# KCVGA_1_1.net
KiCad netlist of a schematic drawn in EAGLE
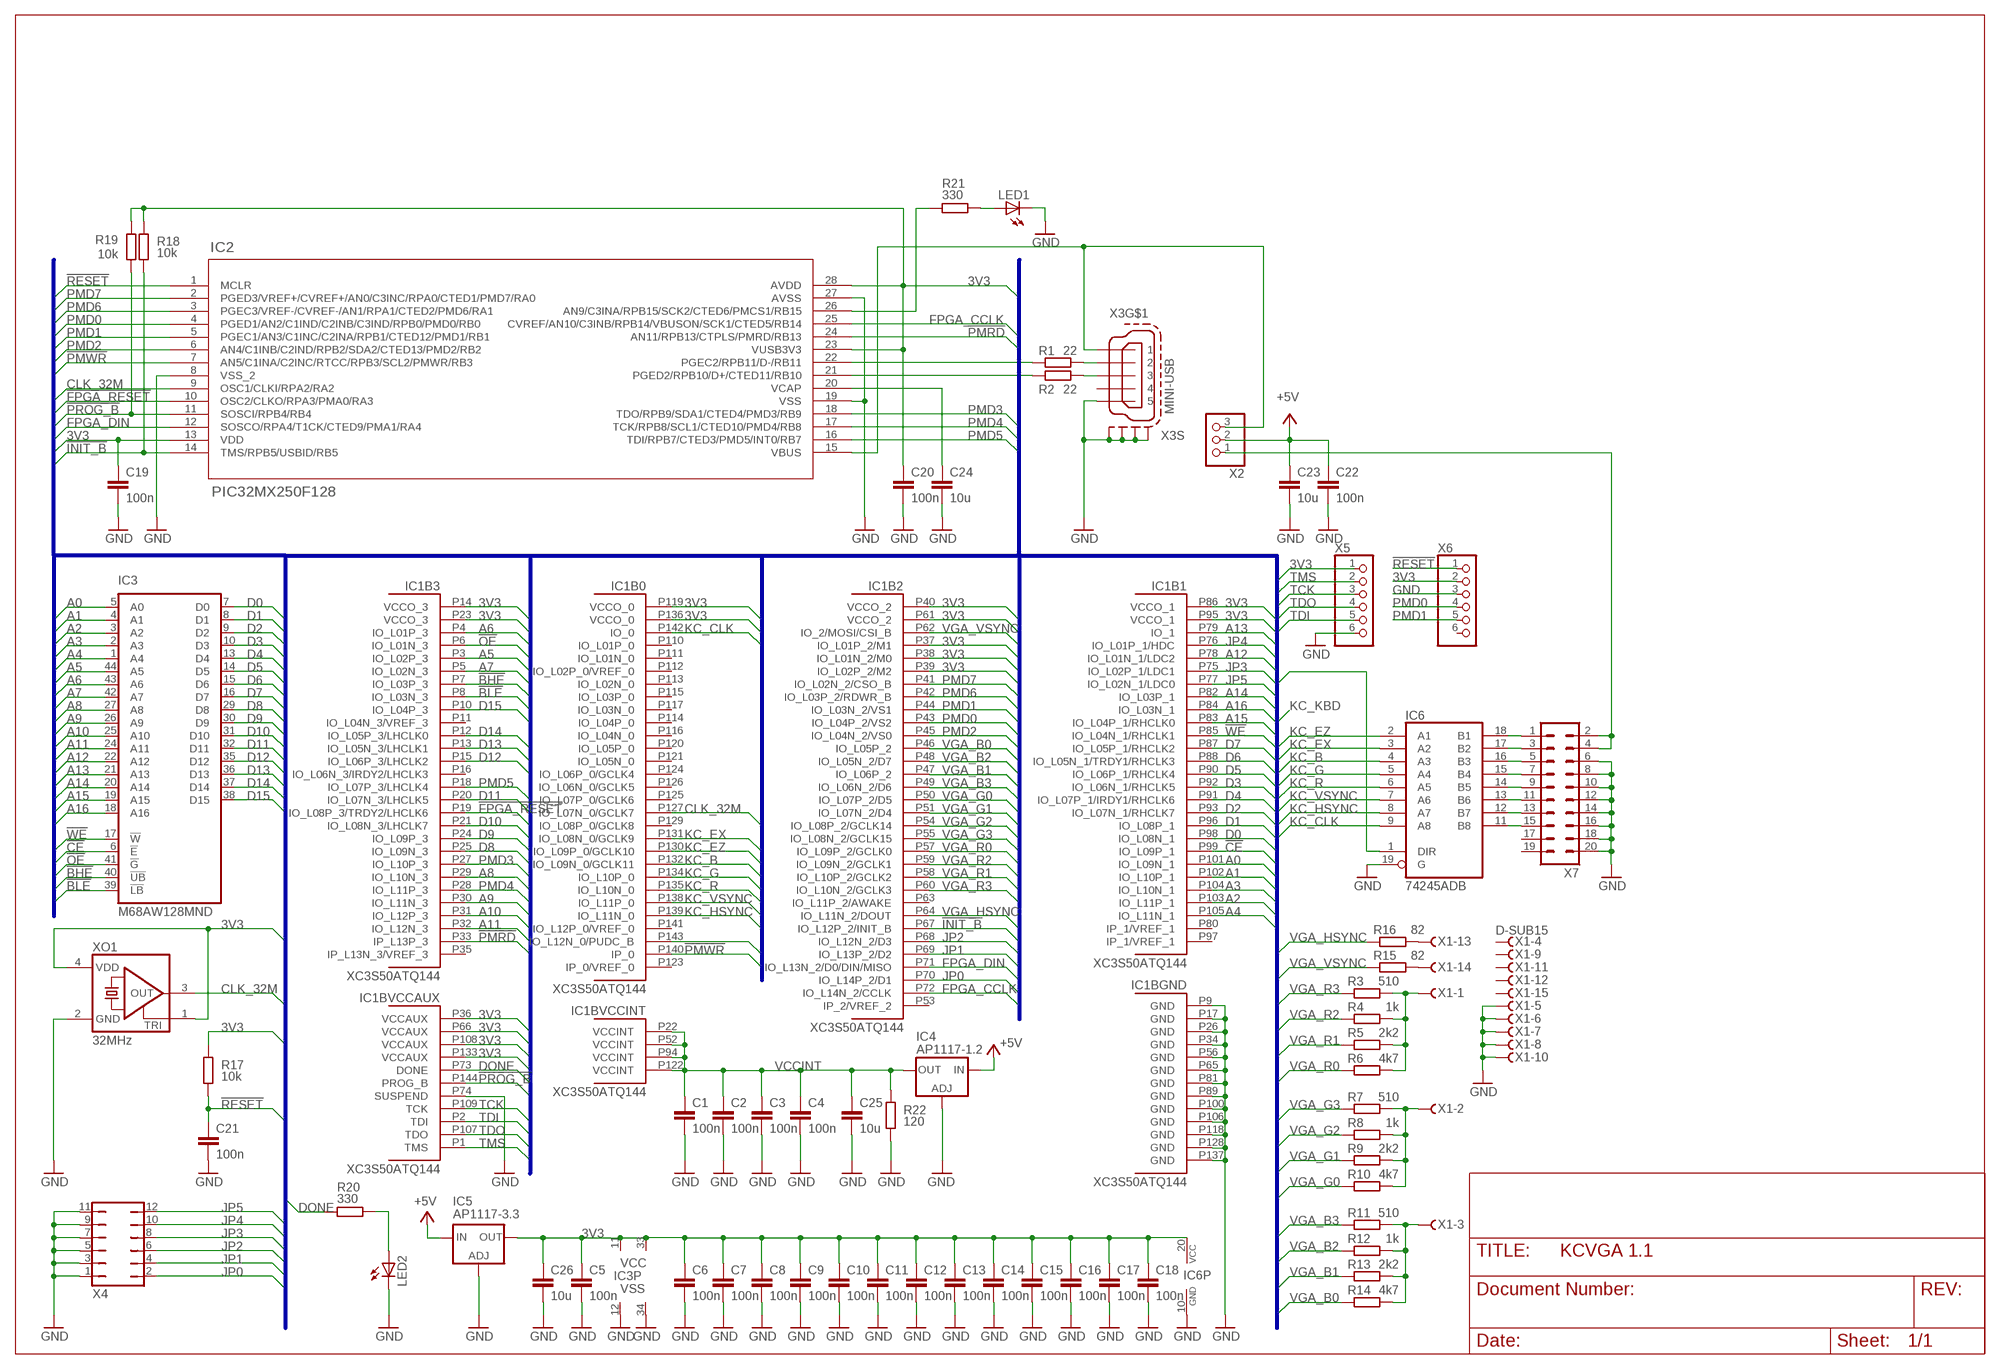
[diagram p0: schematic, sheet 1]

(export (version "E")
  (design (tool "Eeschema 10.0.6"))
  (components
    (comp (ref "C1")
      (value "100n")
      (footprint "eagle-import:C0603K")
      (libsource (lib "eagle-import") (part "C-EUC0603K"))
    )
    (comp (ref "C2")
      (value "100n")
      (footprint "eagle-import:C0603K")
      (libsource (lib "eagle-import") (part "C-EUC0603K"))
    )
    (comp (ref "C3")
      (value "100n")
      (footprint "eagle-import:C0603K")
      (libsource (lib "eagle-import") (part "C-EUC0603K"))
    )
    (comp (ref "C4")
      (value "100n")
      (footprint "eagle-import:C0603K")
      (libsource (lib "eagle-import") (part "C-EUC0603K"))
    )
    (comp (ref "C5")
      (value "100n")
      (footprint "eagle-import:C0603K")
      (libsource (lib "eagle-import") (part "C-EUC0603K"))
    )
    (comp (ref "C6")
      (value "100n")
      (footprint "eagle-import:C0603K")
      (libsource (lib "eagle-import") (part "C-EUC0603K"))
    )
    (comp (ref "C7")
      (value "100n")
      (footprint "eagle-import:C0603K")
      (libsource (lib "eagle-import") (part "C-EUC0603K"))
    )
    (comp (ref "C8")
      (value "100n")
      (footprint "eagle-import:C0603K")
      (libsource (lib "eagle-import") (part "C-EUC0603K"))
    )
    (comp (ref "C9")
      (value "100n")
      (footprint "eagle-import:C0603K")
      (libsource (lib "eagle-import") (part "C-EUC0603K"))
    )
    (comp (ref "C10")
      (value "100n")
      (footprint "eagle-import:C0603K")
      (libsource (lib "eagle-import") (part "C-EUC0603K"))
    )
    (comp (ref "C11")
      (value "100n")
      (footprint "eagle-import:C0603K")
      (libsource (lib "eagle-import") (part "C-EUC0603K"))
    )
    (comp (ref "C12")
      (value "100n")
      (footprint "eagle-import:C0603K")
      (libsource (lib "eagle-import") (part "C-EUC0603K"))
    )
    (comp (ref "C13")
      (value "100n")
      (footprint "eagle-import:C0603K")
      (libsource (lib "eagle-import") (part "C-EUC0603K"))
    )
    (comp (ref "C14")
      (value "100n")
      (footprint "eagle-import:C0603K")
      (libsource (lib "eagle-import") (part "C-EUC0603K"))
    )
    (comp (ref "C15")
      (value "100n")
      (footprint "eagle-import:C0603K")
      (libsource (lib "eagle-import") (part "C-EUC0603K"))
    )
    (comp (ref "C16")
      (value "100n")
      (footprint "eagle-import:C0603K")
      (libsource (lib "eagle-import") (part "C-EUC0603K"))
    )
    (comp (ref "C17")
      (value "100n")
      (footprint "eagle-import:C0603K")
      (libsource (lib "eagle-import") (part "C-EUC0603K"))
    )
    (comp (ref "C18")
      (value "100n")
      (footprint "eagle-import:C0603K")
      (libsource (lib "eagle-import") (part "C-EUC0603K"))
    )
    (comp (ref "C19")
      (value "100n")
      (footprint "eagle-import:C0603K")
      (libsource (lib "eagle-import") (part "C-EUC0603K"))
    )
    (comp (ref "C20")
      (value "100n")
      (footprint "eagle-import:C0603K")
      (libsource (lib "eagle-import") (part "C-EUC0603K"))
    )
    (comp (ref "C21")
      (value "100n")
      (footprint "eagle-import:C0603K")
      (libsource (lib "eagle-import") (part "C-EUC0603K"))
    )
    (comp (ref "C22")
      (value "100n")
      (footprint "eagle-import:C0603K")
      (libsource (lib "eagle-import") (part "C-EUC0603K"))
    )
    (comp (ref "C23")
      (value "10u")
      (footprint "eagle-import:C1206K")
      (libsource (lib "eagle-import") (part "C-EUC1206K"))
    )
    (comp (ref "C24")
      (value "10u")
      (footprint "eagle-import:C1206K")
      (libsource (lib "eagle-import") (part "C-EUC1206K"))
    )
    (comp (ref "C25")
      (value "10u")
      (footprint "eagle-import:C1206K")
      (libsource (lib "eagle-import") (part "C-EUC1206K"))
    )
    (comp (ref "C26")
      (value "10u")
      (footprint "eagle-import:C1206K")
      (libsource (lib "eagle-import") (part "C-EUC1206K"))
    )
    (comp (ref "IC1")
      (value "XC3S50ATQ144")
      (footprint "eagle-import:TQ144")
      (libsource (lib "eagle-import") (part "XC3S50ATQ144"))
    )
    (comp (ref "IC2")
      (value "PIC32MX250F128")
      (footprint "eagle-import:SSOP28_MC")
      (libsource (lib "eagle-import") (part "PIC32MX250F128B_I_SS"))
    )
    (comp (ref "IC3")
      (value "M68AW128MND")
      (footprint "eagle-import:TSOP44-II")
      (libsource (lib "eagle-import") (part "M68AW128MND"))
    )
    (comp (ref "IC4")
      (value "AP1117-1.2")
      (footprint "eagle-import:SOT223")
      (libsource (lib "eagle-import") (part "LD117A?S12TR"))
    )
    (comp (ref "IC5")
      (value "AP1117-3.3")
      (footprint "eagle-import:SOT223")
      (libsource (lib "eagle-import") (part "LD117A?S33TR"))
    )
    (comp (ref "IC6")
      (value "74245ADB")
      (footprint "eagle-import:SSOP20D8")
      (libsource (lib "eagle-import") (part "74245ADB"))
    )
    (comp (ref "LED1")
      (value "LEDCHIPLED_0603")
      (footprint "eagle-import:CHIPLED_0603")
      (libsource (lib "eagle-import") (part "LEDCHIPLED_0603"))
    )
    (comp (ref "LED2")
      (value "LEDCHIPLED_0603")
      (footprint "eagle-import:CHIPLED_0603")
      (libsource (lib "eagle-import") (part "LEDCHIPLED_0603"))
    )
    (comp (ref "R1")
      (value "22")
      (footprint "eagle-import:R0603")
      (libsource (lib "eagle-import") (part "R-EU_R0603"))
    )
    (comp (ref "R2")
      (value "22")
      (footprint "eagle-import:R0603")
      (libsource (lib "eagle-import") (part "R-EU_R0603"))
    )
    (comp (ref "R3")
      (value "510")
      (footprint "eagle-import:R0603")
      (libsource (lib "eagle-import") (part "R-EU_R0603"))
    )
    (comp (ref "R4")
      (value "1k")
      (footprint "eagle-import:R0603")
      (libsource (lib "eagle-import") (part "R-EU_R0603"))
    )
    (comp (ref "R5")
      (value "2k2")
      (footprint "eagle-import:R0603")
      (libsource (lib "eagle-import") (part "R-EU_R0603"))
    )
    (comp (ref "R6")
      (value "4k7")
      (footprint "eagle-import:R0603")
      (libsource (lib "eagle-import") (part "R-EU_R0603"))
    )
    (comp (ref "R7")
      (value "510")
      (footprint "eagle-import:R0603")
      (libsource (lib "eagle-import") (part "R-EU_R0603"))
    )
    (comp (ref "R8")
      (value "1k")
      (footprint "eagle-import:R0603")
      (libsource (lib "eagle-import") (part "R-EU_R0603"))
    )
    (comp (ref "R9")
      (value "2k2")
      (footprint "eagle-import:R0603")
      (libsource (lib "eagle-import") (part "R-EU_R0603"))
    )
    (comp (ref "R10")
      (value "4k7")
      (footprint "eagle-import:R0603")
      (libsource (lib "eagle-import") (part "R-EU_R0603"))
    )
    (comp (ref "R11")
      (value "510")
      (footprint "eagle-import:R0603")
      (libsource (lib "eagle-import") (part "R-EU_R0603"))
    )
    (comp (ref "R12")
      (value "1k")
      (footprint "eagle-import:R0603")
      (libsource (lib "eagle-import") (part "R-EU_R0603"))
    )
    (comp (ref "R13")
      (value "2k2")
      (footprint "eagle-import:R0603")
      (libsource (lib "eagle-import") (part "R-EU_R0603"))
    )
    (comp (ref "R14")
      (value "4k7")
      (footprint "eagle-import:R0603")
      (libsource (lib "eagle-import") (part "R-EU_R0603"))
    )
    (comp (ref "R15")
      (value "82")
      (footprint "eagle-import:R0603")
      (libsource (lib "eagle-import") (part "R-EU_R0603"))
    )
    (comp (ref "R16")
      (value "82")
      (footprint "eagle-import:R0603")
      (libsource (lib "eagle-import") (part "R-EU_R0603"))
    )
    (comp (ref "R17")
      (value "10k")
      (footprint "eagle-import:R0603")
      (libsource (lib "eagle-import") (part "R-EU_R0603"))
    )
    (comp (ref "R18")
      (value "10k")
      (footprint "eagle-import:R0603")
      (libsource (lib "eagle-import") (part "R-EU_R0603"))
    )
    (comp (ref "R19")
      (value "10k")
      (footprint "eagle-import:R0603")
      (libsource (lib "eagle-import") (part "R-EU_R0603"))
    )
    (comp (ref "R20")
      (value "330")
      (footprint "eagle-import:R0603")
      (libsource (lib "eagle-import") (part "R-EU_R0603"))
    )
    (comp (ref "R21")
      (value "330")
      (footprint "eagle-import:R0603")
      (libsource (lib "eagle-import") (part "R-EU_R0603"))
    )
    (comp (ref "R22")
      (value "120")
      (footprint "eagle-import:R0603")
      (libsource (lib "eagle-import") (part "R-EU_R0603"))
    )
    (comp (ref "X1")
      (value "D-SUB15")
      (footprint "eagle-import:HDR15RA")
      (libsource (lib "eagle-import") (part "D-SUB15-HDR15RA"))
    )
    (comp (ref "X2")
      (value "PINHD-1X3")
      (footprint "eagle-import:1X03")
      (libsource (lib "eagle-import") (part "PINHD-1X3"))
    )
    (comp (ref "X3")
      (value "MINI-USB")
      (footprint "eagle-import:32005-301")
      (libsource (lib "eagle-import") (part "MINI-USB-SCHIELD-32005-301"))
    )
    (comp (ref "X4")
      (value "JP6Q")
      (footprint "eagle-import:JP6Q")
      (libsource (lib "eagle-import") (part "JP6Q"))
    )
    (comp (ref "X5")
      (value "PINHD-1X6")
      (footprint "eagle-import:1X06")
      (libsource (lib "eagle-import") (part "PINHD-1X6"))
    )
    (comp (ref "X6")
      (value "PINHD-1X6")
      (footprint "eagle-import:1X06")
      (libsource (lib "eagle-import") (part "PINHD-1X6"))
    )
    (comp (ref "X7")
      (value "ML20")
      (footprint "eagle-import:ML20")
      (libsource (lib "eagle-import") (part "ML20"))
    )
    (comp (ref "XO1")
      (value "32MHz")
      (footprint "eagle-import:ASE")
      (libsource (lib "eagle-import") (part "ASE"))
    )
  )
  (nets
    (net (code "1") (name "+5V") (class "Default")
      (node (ref "C22") (pin "1") (pinfunction "1_1") (pintype "passive"))
      (node (ref "C23") (pin "1") (pinfunction "1_1") (pintype "passive"))
      (node (ref "IC4") (pin "3") (pinfunction "IN_3") (pintype "input"))
      (node (ref "IC5") (pin "3") (pinfunction "IN_3") (pintype "input"))
      (node (ref "X2") (pin "2") (pinfunction "2_2") (pintype "passive"))
    )
    (net (code "2") (name "/3V3") (class "Default")
      (node (ref "C10") (pin "1") (pinfunction "1_1") (pintype "passive"))
      (node (ref "C11") (pin "1") (pinfunction "1_1") (pintype "passive"))
      (node (ref "C12") (pin "1") (pinfunction "1_1") (pintype "passive"))
      (node (ref "C13") (pin "1") (pinfunction "1_1") (pintype "passive"))
      (node (ref "C14") (pin "1") (pinfunction "1_1") (pintype "passive"))
      (node (ref "C15") (pin "1") (pinfunction "1_1") (pintype "passive"))
      (node (ref "C16") (pin "1") (pinfunction "1_1") (pintype "passive"))
      (node (ref "C17") (pin "1") (pinfunction "1_1") (pintype "passive"))
      (node (ref "C18") (pin "1") (pinfunction "1_1") (pintype "passive"))
      (node (ref "C19") (pin "1") (pinfunction "1_1") (pintype "passive"))
      (node (ref "C20") (pin "1") (pinfunction "1_1") (pintype "passive"))
      (node (ref "C26") (pin "1") (pinfunction "1_1") (pintype "passive"))
      (node (ref "C5") (pin "1") (pinfunction "1_1") (pintype "passive"))
      (node (ref "C6") (pin "1") (pinfunction "1_1") (pintype "passive"))
      (node (ref "C7") (pin "1") (pinfunction "1_1") (pintype "passive"))
      (node (ref "C8") (pin "1") (pinfunction "1_1") (pintype "passive"))
      (node (ref "C9") (pin "1") (pinfunction "1_1") (pintype "passive"))
      (node (ref "IC1") (pin "P108") (pinfunction "VCCAUX_P108") (pintype "input"))
      (node (ref "IC1") (pin "P119") (pinfunction "VCCO_0_P119") (pintype "input"))
      (node (ref "IC1") (pin "P133") (pinfunction "VCCAUX_P133") (pintype "input"))
      (node (ref "IC1") (pin "P136") (pinfunction "VCCO_0_P136") (pintype "input"))
      (node (ref "IC1") (pin "P14") (pinfunction "VCCO_3_P14") (pintype "input"))
      (node (ref "IC1") (pin "P143") (pinfunction "IO_L12N_0/PUDC_B_P143") (pintype "bidirectional"))
      (node (ref "IC1") (pin "P23") (pinfunction "VCCO_3_P23") (pintype "input"))
      (node (ref "IC1") (pin "P36") (pinfunction "VCCAUX_P36") (pintype "input"))
      (node (ref "IC1") (pin "P37") (pinfunction "IO_L01P_2/M1_P37") (pintype "bidirectional"))
      (node (ref "IC1") (pin "P38") (pinfunction "IO_L01N_2/M0_P38") (pintype "bidirectional"))
      (node (ref "IC1") (pin "P39") (pinfunction "IO_L02P_2/M2_P39") (pintype "bidirectional"))
      (node (ref "IC1") (pin "P40") (pinfunction "VCCO_2_P40") (pintype "input"))
      (node (ref "IC1") (pin "P61") (pinfunction "VCCO_2_P61") (pintype "input"))
      (node (ref "IC1") (pin "P66") (pinfunction "VCCAUX_P66") (pintype "input"))
      (node (ref "IC1") (pin "P86") (pinfunction "VCCO_1_P86") (pintype "input"))
      (node (ref "IC1") (pin "P95") (pinfunction "VCCO_1_P95") (pintype "input"))
      (node (ref "IC2") (pin "13") (pinfunction "VDD_13") (pintype "power_in"))
      (node (ref "IC2") (pin "23") (pinfunction "VUSB3V3_23") (pintype "power_in"))
      (node (ref "IC2") (pin "28") (pinfunction "AVDD_28") (pintype "power_in"))
      (node (ref "IC3") (pin "11") (pinfunction "VCC_11") (pintype "power_in"))
      (node (ref "IC3") (pin "33") (pinfunction "VCC_33") (pintype "power_in"))
      (node (ref "IC5") (pin "4") (pinfunction "OUT_4") (pintype "passive"))
      (node (ref "IC6") (pin "1") (pinfunction "DIR_1") (pintype "input"))
      (node (ref "IC6") (pin "20") (pinfunction "VCC_20") (pintype "power_in"))
      (node (ref "R17") (pin "2") (pinfunction "2_2") (pintype "passive"))
      (node (ref "R18") (pin "2") (pinfunction "2_2") (pintype "passive"))
      (node (ref "R19") (pin "2") (pinfunction "2_2") (pintype "passive"))
      (node (ref "X5") (pin "1") (pinfunction "1_1") (pintype "passive"))
      (node (ref "X6") (pin "2") (pinfunction "2_2") (pintype "passive"))
      (node (ref "XO1") (pin "1") (pinfunction "TRI_1") (pintype "input"))
      (node (ref "XO1") (pin "4") (pinfunction "VDD_4") (pintype "power_in"))
    )
    (net (code "3") (name "/A0") (class "Default")
      (node (ref "IC1") (pin "P101") (pinfunction "IO_L09N_1_P101") (pintype "bidirectional"))
      (node (ref "IC3") (pin "5") (pinfunction "A0_5") (pintype "input"))
    )
    (net (code "4") (name "/A1") (class "Default")
      (node (ref "IC1") (pin "P102") (pinfunction "IO_L10P_1_P102") (pintype "bidirectional"))
      (node (ref "IC3") (pin "4") (pinfunction "A1_4") (pintype "input"))
    )
    (net (code "5") (name "/A2") (class "Default")
      (node (ref "IC1") (pin "P103") (pinfunction "IO_L11P_1_P103") (pintype "bidirectional"))
      (node (ref "IC3") (pin "3") (pinfunction "A2_3") (pintype "input"))
    )
    (net (code "6") (name "/A3") (class "Default")
      (node (ref "IC1") (pin "P104") (pinfunction "IO_L10N_1_P104") (pintype "bidirectional"))
      (node (ref "IC3") (pin "2") (pinfunction "A3_2") (pintype "input"))
    )
    (net (code "7") (name "/A4") (class "Default")
      (node (ref "IC1") (pin "P105") (pinfunction "IO_L11N_1_P105") (pintype "bidirectional"))
      (node (ref "IC3") (pin "1") (pinfunction "A4_1") (pintype "input"))
    )
    (net (code "8") (name "/A5") (class "Default")
      (node (ref "IC1") (pin "P3") (pinfunction "IO_L02P_3_P3") (pintype "bidirectional"))
      (node (ref "IC3") (pin "44") (pinfunction "A5_44") (pintype "input"))
    )
    (net (code "9") (name "/A6") (class "Default")
      (node (ref "IC1") (pin "P4") (pinfunction "IO_L01P_3_P4") (pintype "bidirectional"))
      (node (ref "IC3") (pin "43") (pinfunction "A6_43") (pintype "input"))
    )
    (net (code "10") (name "/A7") (class "Default")
      (node (ref "IC1") (pin "P5") (pinfunction "IO_L02N_3_P5") (pintype "bidirectional"))
      (node (ref "IC3") (pin "42") (pinfunction "A7_42") (pintype "input"))
    )
    (net (code "11") (name "/A8") (class "Default")
      (node (ref "IC1") (pin "P29") (pinfunction "IO_L10N_3_P29") (pintype "bidirectional"))
      (node (ref "IC3") (pin "27") (pinfunction "A8_27") (pintype "input"))
    )
    (net (code "12") (name "/A9") (class "Default")
      (node (ref "IC1") (pin "P30") (pinfunction "IO_L11N_3_P30") (pintype "bidirectional"))
      (node (ref "IC3") (pin "26") (pinfunction "A9_26") (pintype "input"))
    )
    (net (code "13") (name "/A10") (class "Default")
      (node (ref "IC1") (pin "P31") (pinfunction "IO_L12P_3_P31") (pintype "bidirectional"))
      (node (ref "IC3") (pin "25") (pinfunction "A10_25") (pintype "input"))
    )
    (net (code "14") (name "/A11") (class "Default")
      (node (ref "IC1") (pin "P32") (pinfunction "IO_L12N_3_P32") (pintype "bidirectional"))
      (node (ref "IC3") (pin "24") (pinfunction "A11_24") (pintype "input"))
    )
    (net (code "15") (name "/A12") (class "Default")
      (node (ref "IC1") (pin "P78") (pinfunction "IO_L01N_1/LDC2_P78") (pintype "bidirectional"))
      (node (ref "IC3") (pin "22") (pinfunction "A12_22") (pintype "input"))
    )
    (net (code "16") (name "/A13") (class "Default")
      (node (ref "IC1") (pin "P79") (pinfunction "IO_1_P79") (pintype "bidirectional"))
      (node (ref "IC3") (pin "21") (pinfunction "A13_21") (pintype "input"))
    )
    (net (code "17") (name "/A14") (class "Default")
      (node (ref "IC1") (pin "P82") (pinfunction "IO_L03P_1_P82") (pintype "bidirectional"))
      (node (ref "IC3") (pin "20") (pinfunction "A14_20") (pintype "input"))
    )
    (net (code "18") (name "/A15") (class "Default")
      (node (ref "IC1") (pin "P83") (pinfunction "IO_L04P_1/RHCLK0_P83") (pintype "bidirectional"))
      (node (ref "IC3") (pin "19") (pinfunction "A15_19") (pintype "input"))
    )
    (net (code "19") (name "/A16") (class "Default")
      (node (ref "IC1") (pin "P84") (pinfunction "IO_L03N_1_P84") (pintype "bidirectional"))
      (node (ref "IC3") (pin "18") (pinfunction "A16_18") (pintype "input"))
    )
    (net (code "20") (name "/CLK_32M") (class "Default")
      (node (ref "IC1") (pin "P127") (pinfunction "IO_L07N_0/GCLK7_P127") (pintype "bidirectional"))
      (node (ref "IC2") (pin "9") (pinfunction "OSC1/CLKI/RPA2/RA2_9") (pintype "bidirectional"))
      (node (ref "XO1") (pin "3") (pinfunction "OUT_3") (pintype "output"))
    )
    (net (code "21") (name "/D0") (class "Default")
      (node (ref "IC1") (pin "P98") (pinfunction "IO_L08N_1_P98") (pintype "bidirectional"))
      (node (ref "IC3") (pin "7") (pinfunction "D0_7") (pintype "tri_state"))
    )
    (net (code "22") (name "/D1") (class "Default")
      (node (ref "IC1") (pin "P96") (pinfunction "IO_L08P_1_P96") (pintype "bidirectional"))
      (node (ref "IC3") (pin "8") (pinfunction "D1_8") (pintype "tri_state"))
    )
    (net (code "23") (name "/D2") (class "Default")
      (node (ref "IC1") (pin "P93") (pinfunction "IO_L07N_1/RHCLK7_P93") (pintype "bidirectional"))
      (node (ref "IC3") (pin "9") (pinfunction "D2_9") (pintype "tri_state"))
    )
    (net (code "24") (name "/D3") (class "Default")
      (node (ref "IC1") (pin "P92") (pinfunction "IO_L06N_1/RHCLK5_P92") (pintype "bidirectional"))
      (node (ref "IC3") (pin "10") (pinfunction "D3_10") (pintype "tri_state"))
    )
    (net (code "25") (name "/D4") (class "Default")
      (node (ref "IC1") (pin "P91") (pinfunction "IO_L07P_1/IRDY1/RHCLK6_P91") (pintype "bidirectional"))
      (node (ref "IC3") (pin "13") (pinfunction "D4_13") (pintype "tri_state"))
    )
    (net (code "26") (name "/D5") (class "Default")
      (node (ref "IC1") (pin "P90") (pinfunction "IO_L06P_1/RHCLK4_P90") (pintype "bidirectional"))
      (node (ref "IC3") (pin "14") (pinfunction "D5_14") (pintype "tri_state"))
    )
    (net (code "27") (name "/D6") (class "Default")
      (node (ref "IC1") (pin "P88") (pinfunction "IO_L05N_1/TRDY1/RHCLK3_P88") (pintype "bidirectional"))
      (node (ref "IC3") (pin "15") (pinfunction "D6_15") (pintype "tri_state"))
    )
    (net (code "28") (name "/D7") (class "Default")
      (node (ref "IC1") (pin "P87") (pinfunction "IO_L05P_1/RHCLK2_P87") (pintype "bidirectional"))
      (node (ref "IC3") (pin "16") (pinfunction "D7_16") (pintype "tri_state"))
    )
    (net (code "29") (name "/D8") (class "Default")
      (node (ref "IC1") (pin "P25") (pinfunction "IO_L09N_3_P25") (pintype "bidirectional"))
      (node (ref "IC3") (pin "29") (pinfunction "D8_29") (pintype "tri_state"))
    )
    (net (code "30") (name "/D9") (class "Default")
      (node (ref "IC1") (pin "P24") (pinfunction "IO_L09P_3_P24") (pintype "bidirectional"))
      (node (ref "IC3") (pin "30") (pinfunction "D9_30") (pintype "tri_state"))
    )
    (net (code "31") (name "/D10") (class "Default")
      (node (ref "IC1") (pin "P21") (pinfunction "IO_L08N_3/LHCLK7_P21") (pintype "bidirectional"))
      (node (ref "IC3") (pin "31") (pinfunction "D10_31") (pintype "tri_state"))
    )
    (net (code "32") (name "/D11") (class "Default")
      (node (ref "IC1") (pin "P20") (pinfunction "IO_L07N_3/LHCLK5_P20") (pintype "bidirectional"))
      (node (ref "IC3") (pin "32") (pinfunction "D11_32") (pintype "tri_state"))
    )
    (net (code "33") (name "/D12") (class "Default")
      (node (ref "IC1") (pin "P15") (pinfunction "IO_L06P_3/LHCLK2_P15") (pintype "bidirectional"))
      (node (ref "IC3") (pin "35") (pinfunction "D12_35") (pintype "tri_state"))
    )
    (net (code "34") (name "/D13") (class "Default")
      (node (ref "IC1") (pin "P13") (pinfunction "IO_L05N_3/LHCLK1_P13") (pintype "bidirectional"))
      (node (ref "IC3") (pin "36") (pinfunction "D13_36") (pintype "tri_state"))
    )
    (net (code "35") (name "/D14") (class "Default")
      (node (ref "IC1") (pin "P12") (pinfunction "IO_L05P_3/LHCLK0_P12") (pintype "bidirectional"))
      (node (ref "IC3") (pin "37") (pinfunction "D14_37") (pintype "tri_state"))
    )
    (net (code "36") (name "/D15") (class "Default")
      (node (ref "IC1") (pin "P10") (pinfunction "IO_L04P_3_P10") (pintype "bidirectional"))
      (node (ref "IC3") (pin "38") (pinfunction "D15_38") (pintype "tri_state"))
    )
    (net (code "37") (name "/DONE") (class "Default")
      (node (ref "IC1") (pin "P73") (pinfunction "DONE_P73") (pintype "bidirectional"))
      (node (ref "R20") (pin "1") (pinfunction "1_1") (pintype "passive"))
    )
    (net (code "38") (name "/FPGA_CCLK") (class "Default")
      (node (ref "IC1") (pin "P72") (pinfunction "IO_L14N_2/CCLK_P72") (pintype "bidirectional"))
      (node (ref "IC2") (pin "25") (pinfunction "CVREF/AN10/C3INB/RPB14/VBUSON/SCK1/CTED5/RB14_25") (pintype "bidirectional"))
    )
    (net (code "39") (name "/FPGA_DIN") (class "Default")
      (node (ref "IC1") (pin "P71") (pinfunction "IO_L13N_2/D0/DIN/MISO_P71") (pintype "bidirectional"))
      (node (ref "IC2") (pin "12") (pinfunction "SOSCO/RPA4/T1CK/CTED9/PMA1/RA4_12") (pintype "bidirectional"))
    )
    (net (code "40") (name "/JP0") (class "Default")
      (node (ref "IC1") (pin "P70") (pinfunction "IO_L14P_2/D1_P70") (pintype "bidirectional"))
      (node (ref "X4") (pin "2") (pinfunction "2_2") (pintype "passive"))
    )
    (net (code "41") (name "/JP1") (class "Default")
      (node (ref "IC1") (pin "P69") (pinfunction "IO_L13P_2/D2_P69") (pintype "bidirectional"))
      (node (ref "X4") (pin "4") (pinfunction "4_4") (pintype "passive"))
    )
    (net (code "42") (name "/JP2") (class "Default")
      (node (ref "IC1") (pin "P68") (pinfunction "IO_L12N_2/D3_P68") (pintype "bidirectional"))
      (node (ref "X4") (pin "6") (pinfunction "6_6") (pintype "passive"))
    )
    (net (code "43") (name "/JP3") (class "Default")
      (node (ref "IC1") (pin "P75") (pinfunction "IO_L02P_1/LDC1_P75") (pintype "bidirectional"))
      (node (ref "X4") (pin "8") (pinfunction "8_8") (pintype "passive"))
    )
    (net (code "44") (name "/JP4") (class "Default")
      (node (ref "IC1") (pin "P76") (pinfunction "IO_L01P_1/HDC_P76") (pintype "bidirectional"))
      (node (ref "X4") (pin "10") (pinfunction "10_10") (pintype "passive"))
    )
    (net (code "45") (name "/JP5") (class "Default")
      (node (ref "IC1") (pin "P77") (pinfunction "IO_L02N_1/LDC0_P77") (pintype "bidirectional"))
      (node (ref "X4") (pin "12") (pinfunction "12_12") (pintype "passive"))
    )
    (net (code "46") (name "/KC_B") (class "Default")
      (node (ref "IC1") (pin "P132") (pinfunction "IO_L09N_0/GCLK11_P132") (pintype "bidirectional"))
      (node (ref "IC6") (pin "4") (pinfunction "A3_4") (pintype "bidirectional"))
    )
    (net (code "47") (name "/KC_CLK") (class "Default")
      (node (ref "IC1") (pin "P142") (pinfunction "IO_0_P142") (pintype "bidirectional"))
      (node (ref "IC6") (pin "9") (pinfunction "A8_9") (pintype "bidirectional"))
    )
    (net (code "48") (name "/KC_EX") (class "Default")
      (node (ref "IC1") (pin "P131") (pinfunction "IO_L08N_0/GCLK9_P131") (pintype "bidirectional"))
      (node (ref "IC6") (pin "3") (pinfunction "A2_3") (pintype "bidirectional"))
    )
    (net (code "49") (name "/KC_EZ") (class "Default")
      (node (ref "IC1") (pin "P130") (pinfunction "IO_L09P_0/GCLK10_P130") (pintype "bidirectional"))
      (node (ref "IC6") (pin "2") (pinfunction "A1_2") (pintype "bidirectional"))
    )
    (net (code "50") (name "/KC_G") (class "Default")
      (node (ref "IC1") (pin "P134") (pinfunction "IO_L10P_0_P134") (pintype "bidirectional"))
      (node (ref "IC6") (pin "5") (pinfunction "A4_5") (pintype "bidirectional"))
    )
    (net (code "51") (name "/KC_HSYNC") (class "Default")
      (node (ref "IC1") (pin "P139") (pinfunction "IO_L11N_0_P139") (pintype "bidirectional"))
      (node (ref "IC6") (pin "8") (pinfunction "A7_8") (pintype "bidirectional"))
    )
    (net (code "53") (name "/KC_R") (class "Default")
      (node (ref "IC1") (pin "P135") (pinfunction "IO_L10N_0_P135") (pintype "bidirectional"))
      (node (ref "IC6") (pin "6") (pinfunction "A5_6") (pintype "bidirectional"))
    )
    (net (code "54") (name "/KC_VSYNC") (class "Default")
      (node (ref "IC1") (pin "P138") (pinfunction "IO_L11P_0_P138") (pintype "bidirectional"))
      (node (ref "IC6") (pin "7") (pinfunction "A6_7") (pintype "bidirectional"))
    )
    (net (code "55") (name "/PMD0") (class "Default")
      (node (ref "IC1") (pin "P43") (pinfunction "IO_L04P_2/VS2_P43") (pintype "bidirectional"))
      (node (ref "IC2") (pin "4") (pinfunction "PGED1/AN2/C1IND/C2INB/C3IND/RPB0/PMD0/RB0_4") (pintype "bidirectional"))
      (node (ref "X6") (pin "4") (pinfunction "4_4") (pintype "passive"))
    )
    (net (code "56") (name "/PMD1") (class "Default")
      (node (ref "IC1") (pin "P44") (pinfunction "IO_L03N_2/VS1_P44") (pintype "bidirectional"))
      (node (ref "IC2") (pin "5") (pinfunction "PGEC1/AN3/C1INC/C2INA/RPB1/CTED12/PMD1/RB1_5") (pintype "bidirectional"))
      (node (ref "X6") (pin "5") (pinfunction "5_5") (pintype "passive"))
    )
    (net (code "57") (name "/PMD2") (class "Default")
      (node (ref "IC1") (pin "P45") (pinfunction "IO_L04N_2/VS0_P45") (pintype "bidirectional"))
      (node (ref "IC2") (pin "6") (pinfunction "AN4/C1INB/C2IND/RPB2/SDA2/CTED13/PMD2/RB2_6") (pintype "bidirectional"))
    )
    (net (code "58") (name "/PMD3") (class "Default")
      (node (ref "IC1") (pin "P27") (pinfunction "IO_L10P_3_P27") (pintype "bidirectional"))
      (node (ref "IC2") (pin "18") (pinfunction "TDO/RPB9/SDA1/CTED4/PMD3/RB9_18") (pintype "bidirectional"))
    )
    (net (code "59") (name "/PMD4") (class "Default")
      (node (ref "IC1") (pin "P28") (pinfunction "IO_L11P_3_P28") (pintype "bidirectional"))
      (node (ref "IC2") (pin "17") (pinfunction "TCK/RPB8/SCL1/CTED10/PMD4/RB8_17") (pintype "bidirectional"))
    )
    (net (code "60") (name "/PMD5") (class "Default")
      (node (ref "IC1") (pin "P18") (pinfunction "IO_L07P_3/LHCLK4_P18") (pintype "bidirectional"))
      (node (ref "IC2") (pin "16") (pinfunction "TDI/RPB7/CTED3/PMD5/INT0/RB7_16") (pintype "bidirectional"))
    )
    (net (code "61") (name "/PMD6") (class "Default")
      (node (ref "IC1") (pin "P42") (pinfunction "IO_L03P_2/RDWR_B_P42") (pintype "bidirectional"))
      (node (ref "IC2") (pin "3") (pinfunction "PGEC3/VREF-/CVREF-/AN1/RPA1/CTED2/PMD6/RA1_3") (pintype "bidirectional"))
    )
    (net (code "62") (name "/PMD7") (class "Default")
      (node (ref "IC1") (pin "P41") (pinfunction "IO_L02N_2/CSO_B_P41") (pintype "bidirectional"))
      (node (ref "IC2") (pin "2") (pinfunction "PGED3/VREF+/CVREF+/AN0/C3INC/RPA0/CTED1/PMD7/RA0_2") (pintype "bidirectional"))
    )
    (net (code "63") (name "/TCK") (class "Default")
      (node (ref "IC1") (pin "P109") (pinfunction "TCK_P109") (pintype "input"))
      (node (ref "X5") (pin "3") (pinfunction "3_3") (pintype "passive"))
    )
    (net (code "64") (name "/TDI") (class "Default")
      (node (ref "IC1") (pin "P2") (pinfunction "TDI_P2") (pintype "input"))
      (node (ref "X5") (pin "5") (pinfunction "5_5") (pintype "passive"))
    )
    (net (code "65") (name "/TDO") (class "Default")
      (node (ref "IC1") (pin "P107") (pinfunction "TDO_P107") (pintype "output"))
      (node (ref "X5") (pin "4") (pinfunction "4_4") (pintype "passive"))
    )
    (net (code "66") (name "/TMS") (class "Default")
      (node (ref "IC1") (pin "P1") (pinfunction "TMS_P1") (pintype "input"))
      (node (ref "X5") (pin "2") (pinfunction "2_2") (pintype "passive"))
    )
    (net (code "67") (name "/VCCINT") (class "Default")
      (node (ref "C1") (pin "1") (pinfunction "1_1") (pintype "passive"))
      (node (ref "C2") (pin "1") (pinfunction "1_1") (pintype "passive"))
      (node (ref "C25") (pin "1") (pinfunction "1_1") (pintype "passive"))
      (node (ref "C3") (pin "1") (pinfunction "1_1") (pintype "passive"))
      (node (ref "C4") (pin "1") (pinfunction "1_1") (pintype "passive"))
      (node (ref "IC1") (pin "P122") (pinfunction "VCCINT_P122") (pintype "input"))
      (node (ref "IC1") (pin "P22") (pinfunction "VCCINT_P22") (pintype "input"))
      (node (ref "IC1") (pin "P52") (pinfunction "VCCINT_P52") (pintype "input"))
      (node (ref "IC1") (pin "P94") (pinfunction "VCCINT_P94") (pintype "input"))
      (node (ref "IC4") (pin "4") (pinfunction "OUT_4") (pintype "passive"))
      (node (ref "R22") (pin "2") (pinfunction "2_2") (pintype "passive"))
    )
    (net (code "68") (name "/VGA_B0") (class "Default")
      (node (ref "IC1") (pin "P46") (pinfunction "IO_L05P_2_P46") (pintype "bidirectional"))
      (node (ref "R14") (pin "1") (pinfunction "1_1") (pintype "passive"))
    )
    (net (code "69") (name "/VGA_B1") (class "Default")
      (node (ref "IC1") (pin "P47") (pinfunction "IO_L06P_2_P47") (pintype "bidirectional"))
      (node (ref "R13") (pin "1") (pinfunction "1_1") (pintype "passive"))
    )
    (net (code "70") (name "/VGA_B2") (class "Default")
      (node (ref "IC1") (pin "P48") (pinfunction "IO_L05N_2/D7_P48") (pintype "bidirectional"))
      (node (ref "R12") (pin "1") (pinfunction "1_1") (pintype "passive"))
    )
    (net (code "71") (name "/VGA_B3") (class "Default")
      (node (ref "IC1") (pin "P49") (pinfunction "IO_L06N_2/D6_P49") (pintype "bidirectional"))
      (node (ref "R11") (pin "1") (pinfunction "1_1") (pintype "passive"))
    )
    (net (code "72") (name "/VGA_G0") (class "Default")
      (node (ref "IC1") (pin "P50") (pinfunction "IO_L07P_2/D5_P50") (pintype "bidirectional"))
      (node (ref "R10") (pin "1") (pinfunction "1_1") (pintype "passive"))
    )
    (net (code "73") (name "/VGA_G1") (class "Default")
      (node (ref "IC1") (pin "P51") (pinfunction "IO_L07N_2/D4_P51") (pintype "bidirectional"))
      (node (ref "R9") (pin "1") (pinfunction "1_1") (pintype "passive"))
    )
    (net (code "74") (name "/VGA_G2") (class "Default")
      (node (ref "IC1") (pin "P54") (pinfunction "IO_L08P_2/GCLK14_P54") (pintype "bidirectional"))
      (node (ref "R8") (pin "1") (pinfunction "1_1") (pintype "passive"))
    )
    (net (code "75") (name "/VGA_G3") (class "Default")
      (node (ref "IC1") (pin "P55") (pinfunction "IO_L08N_2/GCLK15_P55") (pintype "bidirectional"))
      (node (ref "R7") (pin "1") (pinfunction "1_1") (pintype "passive"))
    )
    (net (code "76") (name "/VGA_HSYNC") (class "Default")
      (node (ref "IC1") (pin "P64") (pinfunction "IO_L11N_2/DOUT_P64") (pintype "bidirectional"))
      (node (ref "R16") (pin "1") (pinfunction "1_1") (pintype "passive"))
    )
    (net (code "77") (name "/VGA_R0") (class "Default")
      (node (ref "IC1") (pin "P57") (pinfunction "IO_L09P_2/GCLK0_P57") (pintype "bidirectional"))
      (node (ref "R6") (pin "1") (pinfunction "1_1") (pintype "passive"))
    )
    (net (code "78") (name "/VGA_R1") (class "Default")
      (node (ref "IC1") (pin "P58") (pinfunction "IO_L10P_2/GCLK2_P58") (pintype "bidirectional"))
      (node (ref "R5") (pin "1") (pinfunction "1_1") (pintype "passive"))
    )
    (net (code "79") (name "/VGA_R2") (class "Default")
      (node (ref "IC1") (pin "P59") (pinfunction "IO_L09N_2/GCLK1_P59") (pintype "bidirectional"))
      (node (ref "R4") (pin "1") (pinfunction "1_1") (pintype "passive"))
    )
    (net (code "80") (name "/VGA_R3") (class "Default")
      (node (ref "IC1") (pin "P60") (pinfunction "IO_L10N_2/GCLK3_P60") (pintype "bidirectional"))
      (node (ref "R3") (pin "1") (pinfunction "1_1") (pintype "passive"))
    )
    (net (code "81") (name "/VGA_VSYNC") (class "Default")
      (node (ref "IC1") (pin "P62") (pinfunction "IO_2/MOSI/CSI_B_P62") (pintype "bidirectional"))
      (node (ref "R15") (pin "1") (pinfunction "1_1") (pintype "passive"))
    )
    (net (code "82") (name "/~{BHE}") (class "Default")
      (node (ref "IC1") (pin "P7") (pinfunction "IO_L03P_3_P7") (pintype "bidirectional"))
      (node (ref "IC3") (pin "40") (pinfunction "~{UB}_40") (pintype "input"))
    )
    (net (code "83") (name "/~{BLE}") (class "Default")
      (node (ref "IC1") (pin "P8") (pinfunction "IO_L03N_3_P8") (pintype "bidirectional"))
      (node (ref "IC3") (pin "39") (pinfunction "~{LB}_39") (pintype "input"))
    )
    (net (code "84") (name "/~{CE}") (class "Default")
      (node (ref "IC1") (pin "P99") (pinfunction "IO_L09P_1_P99") (pintype "bidirectional"))
      (node (ref "IC3") (pin "6") (pinfunction "~{E}_6") (pintype "input"))
    )
    (net (code "85") (name "/~{FPGA_RESET}") (class "Default")
      (node (ref "IC1") (pin "P19") (pinfunction "IO_L08P_3/TRDY2/LHCLK6_P19") (pintype "bidirectional"))
      (node (ref "IC2") (pin "10") (pinfunction "OSC2/CLKO/RPA3/PMA0/RA3_10") (pintype "bidirectional"))
    )
    (net (code "86") (name "/~{INIT_B}") (class "Default")
      (node (ref "IC1") (pin "P67") (pinfunction "IO_L12P_2/INIT_B_P67") (pintype "bidirectional"))
      (node (ref "IC2") (pin "14") (pinfunction "TMS/RPB5/USBID/RB5_14") (pintype "bidirectional"))
      (node (ref "R18") (pin "1") (pinfunction "1_1") (pintype "passive"))
    )
    (net (code "87") (name "/~{OE}") (class "Default")
      (node (ref "IC1") (pin "P6") (pinfunction "IO_L01N_3_P6") (pintype "bidirectional"))
      (node (ref "IC3") (pin "41") (pinfunction "~{G}_41") (pintype "input"))
    )
    (net (code "88") (name "/~{PMRD}") (class "Default")
      (node (ref "IC1") (pin "P33") (pinfunction "IP_L13P_3_P33") (pintype "input"))
      (node (ref "IC2") (pin "24") (pinfunction "AN11/RPB13/CTPLS/PMRD/RB13_24") (pintype "bidirectional"))
    )
    (net (code "89") (name "/~{PMWR}") (class "Default")
      (node (ref "IC1") (pin "P140") (pinfunction "IP_0_P140") (pintype "input"))
      (node (ref "IC2") (pin "7") (pinfunction "AN5/C1INA/C2INC/RTCC/RPB3/SCL2/PMWR/RB3_7") (pintype "bidirectional"))
    )
    (net (code "90") (name "/~{PROG_B}") (class "Default")
      (node (ref "IC1") (pin "P144") (pinfunction "PROG_B_P144") (pintype "input"))
      (node (ref "IC2") (pin "11") (pinfunction "SOSCI/RPB4/RB4_11") (pintype "bidirectional"))
      (node (ref "R19") (pin "1") (pinfunction "1_1") (pintype "passive"))
    )
    (net (code "91") (name "/~{RESET}") (class "Default")
      (node (ref "C21") (pin "1") (pinfunction "1_1") (pintype "passive"))
      (node (ref "IC2") (pin "1") (pinfunction "MCLR_1") (pintype "input"))
      (node (ref "R17") (pin "1") (pinfunction "1_1") (pintype "passive"))
      (node (ref "X6") (pin "1") (pinfunction "1_1") (pintype "passive"))
    )
    (net (code "92") (name "/~{WE}") (class "Default")
      (node (ref "IC1") (pin "P85") (pinfunction "IO_L04N_1/RHCLK1_P85") (pintype "bidirectional"))
      (node (ref "IC3") (pin "17") (pinfunction "~{W}_17") (pintype "input"))
    )
    (net (code "93") (name "GND") (class "Default")
      (node (ref "C1") (pin "2") (pinfunction "2_2") (pintype "passive"))
      (node (ref "C10") (pin "2") (pinfunction "2_2") (pintype "passive"))
      (node (ref "C11") (pin "2") (pinfunction "2_2") (pintype "passive"))
      (node (ref "C12") (pin "2") (pinfunction "2_2") (pintype "passive"))
      (node (ref "C13") (pin "2") (pinfunction "2_2") (pintype "passive"))
      (node (ref "C14") (pin "2") (pinfunction "2_2") (pintype "passive"))
      (node (ref "C15") (pin "2") (pinfunction "2_2") (pintype "passive"))
      (node (ref "C16") (pin "2") (pinfunction "2_2") (pintype "passive"))
      (node (ref "C17") (pin "2") (pinfunction "2_2") (pintype "passive"))
      (node (ref "C18") (pin "2") (pinfunction "2_2") (pintype "passive"))
      (node (ref "C19") (pin "2") (pinfunction "2_2") (pintype "passive"))
      (node (ref "C2") (pin "2") (pinfunction "2_2") (pintype "passive"))
      (node (ref "C20") (pin "2") (pinfunction "2_2") (pintype "passive"))
      (node (ref "C21") (pin "2") (pinfunction "2_2") (pintype "passive"))
      (node (ref "C22") (pin "2") (pinfunction "2_2") (pintype "passive"))
      (node (ref "C23") (pin "2") (pinfunction "2_2") (pintype "passive"))
      (node (ref "C24") (pin "2") (pinfunction "2_2") (pintype "passive"))
      (node (ref "C25") (pin "2") (pinfunction "2_2") (pintype "passive"))
      (node (ref "C26") (pin "2") (pinfunction "2_2") (pintype "passive"))
      (node (ref "C3") (pin "2") (pinfunction "2_2") (pintype "passive"))
      (node (ref "C4") (pin "2") (pinfunction "2_2") (pintype "passive"))
      (node (ref "C5") (pin "2") (pinfunction "2_2") (pintype "passive"))
      (node (ref "C6") (pin "2") (pinfunction "2_2") (pintype "passive"))
      (node (ref "C7") (pin "2") (pinfunction "2_2") (pintype "passive"))
      (node (ref "C8") (pin "2") (pinfunction "2_2") (pintype "passive"))
      (node (ref "C9") (pin "2") (pinfunction "2_2") (pintype "passive"))
      (node (ref "IC1") (pin "P100") (pinfunction "GND_P100") (pintype "power_in"))
      (node (ref "IC1") (pin "P106") (pinfunction "GND_P106") (pintype "power_in"))
      (node (ref "IC1") (pin "P118") (pinfunction "GND_P118") (pintype "power_in"))
      (node (ref "IC1") (pin "P128") (pinfunction "GND_P128") (pintype "power_in"))
      (node (ref "IC1") (pin "P137") (pinfunction "GND_P137") (pintype "power_in"))
      (node (ref "IC1") (pin "P17") (pinfunction "GND_P17") (pintype "power_in"))
      (node (ref "IC1") (pin "P26") (pinfunction "GND_P26") (pintype "power_in"))
      (node (ref "IC1") (pin "P34") (pinfunction "GND_P34") (pintype "power_in"))
      (node (ref "IC1") (pin "P56") (pinfunction "GND_P56") (pintype "power_in"))
      (node (ref "IC1") (pin "P65") (pinfunction "GND_P65") (pintype "power_in"))
      (node (ref "IC1") (pin "P74") (pinfunction "SUSPEND_P74") (pintype "input"))
      (node (ref "IC1") (pin "P81") (pinfunction "GND_P81") (pintype "power_in"))
      (node (ref "IC1") (pin "P89") (pinfunction "GND_P89") (pintype "power_in"))
      (node (ref "IC1") (pin "P9") (pinfunction "GND_P9") (pintype "power_in"))
      (node (ref "IC2") (pin "19") (pinfunction "VSS_19") (pintype "power_in"))
      (node (ref "IC2") (pin "27") (pinfunction "AVSS_27") (pintype "power_in"))
      (node (ref "IC2") (pin "8") (pinfunction "VSS_2_8") (pintype "power_in"))
      (node (ref "IC3") (pin "12") (pinfunction "VSS_12") (pintype "power_in"))
      (node (ref "IC3") (pin "34") (pinfunction "VSS_34") (pintype "power_in"))
      (node (ref "IC4") (pin "1") (pinfunction "ADJ_1") (pintype "input"))
      (node (ref "IC5") (pin "1") (pinfunction "ADJ_1") (pintype "input"))
      (node (ref "IC6") (pin "10") (pinfunction "GND_10") (pintype "power_in"))
      (node (ref "IC6") (pin "19") (pinfunction "G_19") (pintype "input"))
      (node (ref "LED1") (pin "C") (pinfunction "C_C") (pintype "passive"))
      (node (ref "LED2") (pin "C") (pinfunction "C_C") (pintype "passive"))
      (node (ref "R22") (pin "1") (pinfunction "1_1") (pintype "passive"))
      (node (ref "X1") (pin "10") (pinfunction "F_10") (pintype "passive"))
      (node (ref "X1") (pin "5") (pinfunction "F_5") (pintype "passive"))
      (node (ref "X1") (pin "6") (pinfunction "F_6") (pintype "passive"))
      (node (ref "X1") (pin "7") (pinfunction "F_7") (pintype "passive"))
      (node (ref "X1") (pin "8") (pinfunction "F_8") (pintype "passive"))
      (node (ref "X3") (pin "5") (pinfunction "5_5") (pintype "passive"))
      (node (ref "X3") (pin "M1") (pinfunction "S1_M1") (pintype "passive"))
      (node (ref "X3") (pin "M2") (pinfunction "S2_M2") (pintype "passive"))
      (node (ref "X3") (pin "M3") (pinfunction "S3_M3") (pintype "passive"))
      (node (ref "X3") (pin "M4") (pinfunction "S4_M4") (pintype "passive"))
      (node (ref "X4") (pin "1") (pinfunction "1_1") (pintype "passive"))
      (node (ref "X4") (pin "11") (pinfunction "11_11") (pintype "passive"))
      (node (ref "X4") (pin "3") (pinfunction "3_3") (pintype "passive"))
      (node (ref "X4") (pin "5") (pinfunction "5_5") (pintype "passive"))
      (node (ref "X4") (pin "7") (pinfunction "7_7") (pintype "passive"))
      (node (ref "X4") (pin "9") (pinfunction "9_9") (pintype "passive"))
      (node (ref "X5") (pin "6") (pinfunction "6_6") (pintype "passive"))
      (node (ref "X6") (pin "3") (pinfunction "3_3") (pintype "passive"))
      (node (ref "X7") (pin "10") (pinfunction "10_10") (pintype "passive"))
      (node (ref "X7") (pin "12") (pinfunction "12_12") (pintype "passive"))
      (node (ref "X7") (pin "14") (pinfunction "14_14") (pintype "passive"))
      (node (ref "X7") (pin "16") (pinfunction "16_16") (pintype "passive"))
      (node (ref "X7") (pin "18") (pinfunction "18_18") (pintype "passive"))
      (node (ref "X7") (pin "20") (pinfunction "20_20") (pintype "passive"))
      (node (ref "X7") (pin "6") (pinfunction "6_6") (pintype "passive"))
      (node (ref "X7") (pin "8") (pinfunction "8_8") (pintype "passive"))
      (node (ref "XO1") (pin "2") (pinfunction "GND_2") (pintype "power_in"))
    )
    (net (code "94") (name "Net-(IC2-AN9{slash}C3INA{slash}RPB15{slash}SCK2{slash}CTED6{slash}PMCS1{slash}RB15)") (class "Default")
      (node (ref "IC2") (pin "26") (pinfunction "AN9/C3INA/RPB15/SCK2/CTED6/PMCS1/RB15_26") (pintype "bidirectional"))
      (node (ref "R21") (pin "1") (pinfunction "1_1") (pintype "passive"))
    )
    (net (code "95") (name "Net-(IC2-PGEC2{slash}RPB11{slash}D-{slash}RB11)") (class "Default")
      (node (ref "IC2") (pin "22") (pinfunction "PGEC2/RPB11/D-/RB11_22") (pintype "bidirectional"))
      (node (ref "R1") (pin "1") (pinfunction "1_1") (pintype "passive"))
    )
    (net (code "96") (name "Net-(IC2-PGED2{slash}RPB10{slash}D+{slash}CTED11{slash}RB10)") (class "Default")
      (node (ref "IC2") (pin "21") (pinfunction "PGED2/RPB10/D+/CTED11/RB10_21") (pintype "bidirectional"))
      (node (ref "R2") (pin "1") (pinfunction "1_1") (pintype "passive"))
    )
    (net (code "97") (name "Net-(IC2-VBUS)") (class "Default")
      (node (ref "IC2") (pin "15") (pinfunction "VBUS_15") (pintype "power_in"))
      (node (ref "X2") (pin "3") (pinfunction "3_3") (pintype "passive"))
      (node (ref "X3") (pin "1") (pinfunction "1_1") (pintype "passive"))
    )
    (net (code "98") (name "Net-(IC2-VCAP)") (class "Default")
      (node (ref "C24") (pin "1") (pinfunction "1_1") (pintype "passive"))
      (node (ref "IC2") (pin "20") (pinfunction "VCAP_20") (pintype "power_in"))
    )
    (net (code "99") (name "Net-(IC6A-B1)") (class "Default")
      (node (ref "IC6") (pin "18") (pinfunction "B1_18") (pintype "bidirectional"))
      (node (ref "X7") (pin "1") (pinfunction "1_1") (pintype "passive"))
    )
    (net (code "100") (name "Net-(IC6A-B2)") (class "Default")
      (node (ref "IC6") (pin "17") (pinfunction "B2_17") (pintype "bidirectional"))
      (node (ref "X7") (pin "3") (pinfunction "3_3") (pintype "passive"))
    )
    (net (code "101") (name "Net-(IC6A-B3)") (class "Default")
      (node (ref "IC6") (pin "16") (pinfunction "B3_16") (pintype "bidirectional"))
      (node (ref "X7") (pin "5") (pinfunction "5_5") (pintype "passive"))
    )
    (net (code "102") (name "Net-(IC6A-B4)") (class "Default")
      (node (ref "IC6") (pin "15") (pinfunction "B4_15") (pintype "bidirectional"))
      (node (ref "X7") (pin "7") (pinfunction "7_7") (pintype "passive"))
    )
    (net (code "103") (name "Net-(IC6A-B5)") (class "Default")
      (node (ref "IC6") (pin "14") (pinfunction "B5_14") (pintype "bidirectional"))
      (node (ref "X7") (pin "9") (pinfunction "9_9") (pintype "passive"))
    )
    (net (code "104") (name "Net-(IC6A-B6)") (class "Default")
      (node (ref "IC6") (pin "13") (pinfunction "B6_13") (pintype "bidirectional"))
      (node (ref "X7") (pin "11") (pinfunction "11_11") (pintype "passive"))
    )
    (net (code "105") (name "Net-(IC6A-B7)") (class "Default")
      (node (ref "IC6") (pin "12") (pinfunction "B7_12") (pintype "bidirectional"))
      (node (ref "X7") (pin "13") (pinfunction "13_13") (pintype "passive"))
    )
    (net (code "106") (name "Net-(IC6A-B8)") (class "Default")
      (node (ref "IC6") (pin "11") (pinfunction "B8_11") (pintype "bidirectional"))
      (node (ref "X7") (pin "15") (pinfunction "15_15") (pintype "passive"))
    )
    (net (code "107") (name "Net-(LED1-PadA)") (class "Default")
      (node (ref "LED1") (pin "A") (pinfunction "A_A") (pintype "passive"))
      (node (ref "R21") (pin "2") (pinfunction "2_2") (pintype "passive"))
    )
    (net (code "108") (name "Net-(LED2-PadA)") (class "Default")
      (node (ref "LED2") (pin "A") (pinfunction "A_A") (pintype "passive"))
      (node (ref "R20") (pin "2") (pinfunction "2_2") (pintype "passive"))
    )
    (net (code "109") (name "Net-(R1-Pad2)") (class "Default")
      (node (ref "R1") (pin "2") (pinfunction "2_2") (pintype "passive"))
      (node (ref "X3") (pin "2") (pinfunction "2_2") (pintype "passive"))
    )
    (net (code "110") (name "Net-(R2-Pad2)") (class "Default")
      (node (ref "R2") (pin "2") (pinfunction "2_2") (pintype "passive"))
      (node (ref "X3") (pin "3") (pinfunction "3_3") (pintype "passive"))
    )
    (net (code "111") (name "Net-(X1A-F)") (class "Default")
      (node (ref "R3") (pin "2") (pinfunction "2_2") (pintype "passive"))
      (node (ref "R4") (pin "2") (pinfunction "2_2") (pintype "passive"))
      (node (ref "R5") (pin "2") (pinfunction "2_2") (pintype "passive"))
      (node (ref "R6") (pin "2") (pinfunction "2_2") (pintype "passive"))
      (node (ref "X1") (pin "1") (pinfunction "F_1") (pintype "passive"))
    )
    (net (code "112") (name "Net-(X1E-F)") (class "Default")
      (node (ref "R16") (pin "2") (pinfunction "2_2") (pintype "passive"))
      (node (ref "X1") (pin "13") (pinfunction "F_13") (pintype "passive"))
    )
    (net (code "113") (name "Net-(X1F-F)") (class "Default")
      (node (ref "R15") (pin "2") (pinfunction "2_2") (pintype "passive"))
      (node (ref "X1") (pin "14") (pinfunction "F_14") (pintype "passive"))
    )
    (net (code "114") (name "Net-(X1H-F)") (class "Default")
      (node (ref "R10") (pin "2") (pinfunction "2_2") (pintype "passive"))
      (node (ref "R7") (pin "2") (pinfunction "2_2") (pintype "passive"))
      (node (ref "R8") (pin "2") (pinfunction "2_2") (pintype "passive"))
      (node (ref "R9") (pin "2") (pinfunction "2_2") (pintype "passive"))
      (node (ref "X1") (pin "2") (pinfunction "F_2") (pintype "passive"))
    )
    (net (code "115") (name "Net-(X1I-F)") (class "Default")
      (node (ref "R11") (pin "2") (pinfunction "2_2") (pintype "passive"))
      (node (ref "R12") (pin "2") (pinfunction "2_2") (pintype "passive"))
      (node (ref "R13") (pin "2") (pinfunction "2_2") (pintype "passive"))
      (node (ref "R14") (pin "2") (pinfunction "2_2") (pintype "passive"))
      (node (ref "X1") (pin "3") (pinfunction "F_3") (pintype "passive"))
    )
    (net (code "116") (name "Net-(X2-Pad1)") (class "Default")
      (node (ref "X2") (pin "1") (pinfunction "1_1") (pintype "passive"))
      (node (ref "X7") (pin "2") (pinfunction "2_2") (pintype "passive"))
      (node (ref "X7") (pin "4") (pinfunction "4_4") (pintype "passive"))
    )
    (net (code "117") (name "unconnected-(IC1A-IO_L01N_0-PadP111)") (class "Default")
      (node (ref "IC1") (pin "P111") (pinfunction "IO_L01N_0_P111") (pintype "bidirectional"))
    )
    (net (code "118") (name "unconnected-(IC1A-IO_L01P_0-PadP110)") (class "Default")
      (node (ref "IC1") (pin "P110") (pinfunction "IO_L01P_0_P110") (pintype "bidirectional"))
    )
    (net (code "119") (name "unconnected-(IC1A-IO_L02N_0-PadP113)") (class "Default")
      (node (ref "IC1") (pin "P113") (pinfunction "IO_L02N_0_P113") (pintype "bidirectional"))
    )
    (net (code "120") (name "unconnected-(IC1A-IO_L02P_0{slash}VREF_0-PadP112)") (class "Default")
      (node (ref "IC1") (pin "P112") (pinfunction "IO_L02P_0/VREF_0_P112") (pintype "bidirectional"))
    )
    (net (code "121") (name "unconnected-(IC1A-IO_L03N_0-PadP117)") (class "Default")
      (node (ref "IC1") (pin "P117") (pinfunction "IO_L03N_0_P117") (pintype "bidirectional"))
    )
    (net (code "122") (name "unconnected-(IC1A-IO_L03P_0-PadP115)") (class "Default")
      (node (ref "IC1") (pin "P115") (pinfunction "IO_L03P_0_P115") (pintype "bidirectional"))
    )
    (net (code "123") (name "unconnected-(IC1A-IO_L04N_0-PadP116)") (class "Default")
      (node (ref "IC1") (pin "P116") (pinfunction "IO_L04N_0_P116") (pintype "bidirectional"))
    )
    (net (code "124") (name "unconnected-(IC1A-IO_L04P_0-PadP114)") (class "Default")
      (node (ref "IC1") (pin "P114") (pinfunction "IO_L04P_0_P114") (pintype "bidirectional"))
    )
    (net (code "125") (name "unconnected-(IC1A-IO_L05N_0-PadP121)") (class "Default")
      (node (ref "IC1") (pin "P121") (pinfunction "IO_L05N_0_P121") (pintype "bidirectional"))
    )
    (net (code "126") (name "unconnected-(IC1A-IO_L05P_0-PadP120)") (class "Default")
      (node (ref "IC1") (pin "P120") (pinfunction "IO_L05P_0_P120") (pintype "bidirectional"))
    )
    (net (code "127") (name "unconnected-(IC1A-IO_L06N_0{slash}GCLK5-PadP126)") (class "Default")
      (node (ref "IC1") (pin "P126") (pinfunction "IO_L06N_0/GCLK5_P126") (pintype "bidirectional"))
    )
    (net (code "128") (name "unconnected-(IC1A-IO_L06P_0{slash}GCLK4-PadP124)") (class "Default")
      (node (ref "IC1") (pin "P124") (pinfunction "IO_L06P_0/GCLK4_P124") (pintype "bidirectional"))
    )
    (net (code "129") (name "unconnected-(IC1A-IO_L07P_0{slash}GCLK6-PadP125)") (class "Default")
      (node (ref "IC1") (pin "P125") (pinfunction "IO_L07P_0/GCLK6_P125") (pintype "bidirectional"))
    )
    (net (code "130") (name "unconnected-(IC1A-IO_L08P_0{slash}GCLK8-PadP129)") (class "Default")
      (node (ref "IC1") (pin "P129") (pinfunction "IO_L08P_0/GCLK8_P129") (pintype "bidirectional"))
    )
    (net (code "131") (name "unconnected-(IC1A-IO_L12P_0{slash}VREF_0-PadP141)") (class "Default")
      (node (ref "IC1") (pin "P141") (pinfunction "IO_L12P_0/VREF_0_P141") (pintype "bidirectional"))
    )
    (net (code "132") (name "unconnected-(IC1A-IP_0{slash}VREF_0-PadP123)") (class "Default")
      (node (ref "IC1") (pin "P123") (pinfunction "IP_0/VREF_0_P123") (pintype "input"))
    )
    (net (code "133") (name "unconnected-(IC1B-IP_1{slash}VREF_1-PadP80)") (class "Default")
      (node (ref "IC1") (pin "P80") (pinfunction "IP_1/VREF_1_P80") (pintype "input"))
    )
    (net (code "134") (name "unconnected-(IC1B-IP_1{slash}VREF_1-PadP97)") (class "Default")
      (node (ref "IC1") (pin "P97") (pinfunction "IP_1/VREF_1_P97") (pintype "input"))
    )
    (net (code "135") (name "unconnected-(IC1C-IO_L11P_2{slash}AWAKE-PadP63)") (class "Default")
      (node (ref "IC1") (pin "P63") (pinfunction "IO_L11P_2/AWAKE_P63") (pintype "bidirectional"))
    )
    (net (code "136") (name "unconnected-(IC1C-IP_2{slash}VREF_2-PadP53)") (class "Default")
      (node (ref "IC1") (pin "P53") (pinfunction "IP_2/VREF_2_P53") (pintype "input"))
    )
    (net (code "137") (name "unconnected-(IC1D-IO_L04N_3{slash}VREF_3-PadP11)") (class "Default")
      (node (ref "IC1") (pin "P11") (pinfunction "IO_L04N_3/VREF_3_P11") (pintype "bidirectional"))
    )
    (net (code "138") (name "unconnected-(IC1D-IO_L06N_3{slash}IRDY2{slash}LHCLK3-PadP16)") (class "Default")
      (node (ref "IC1") (pin "P16") (pinfunction "IO_L06N_3/IRDY2/LHCLK3_P16") (pintype "bidirectional"))
    )
    (net (code "139") (name "unconnected-(IC1D-IP_L13N_3{slash}VREF_3-PadP35)") (class "Default")
      (node (ref "IC1") (pin "P35") (pinfunction "IP_L13N_3/VREF_3_P35") (pintype "input"))
    )
    (net (code "140") (name "unconnected-(X1C-F-Pad11)") (class "Default")
      (node (ref "X1") (pin "11") (pinfunction "F_11") (pintype "passive"))
    )
    (net (code "141") (name "unconnected-(X1D-F-Pad12)") (class "Default")
      (node (ref "X1") (pin "12") (pinfunction "F_12") (pintype "passive"))
    )
    (net (code "142") (name "unconnected-(X1G-F-Pad15)") (class "Default")
      (node (ref "X1") (pin "15") (pinfunction "F_15") (pintype "passive"))
    )
    (net (code "143") (name "unconnected-(X1J-F-Pad4)") (class "Default")
      (node (ref "X1") (pin "4") (pinfunction "F_4") (pintype "passive"))
    )
    (net (code "144") (name "unconnected-(X1O-F-Pad9)") (class "Default")
      (node (ref "X1") (pin "9") (pinfunction "F_9") (pintype "passive"))
    )
    (net (code "145") (name "unconnected-(X3-Pad4)") (class "Default")
      (node (ref "X3") (pin "4") (pinfunction "4_4") (pintype "passive"))
    )
    (net (code "146") (name "unconnected-(X6-Pad6)") (class "Default")
      (node (ref "X6") (pin "6") (pinfunction "6_6") (pintype "passive"))
    )
    (net (code "147") (name "unconnected-(X7-Pad17)") (class "Default")
      (node (ref "X7") (pin "17") (pinfunction "17_17") (pintype "passive"))
    )
    (net (code "148") (name "unconnected-(X7-Pad19)") (class "Default")
      (node (ref "X7") (pin "19") (pinfunction "19_19") (pintype "passive"))
    )
  )
)
